# roller-shutter-rs485-double.net
KiCad netlist of a schematic drawn in EAGLE
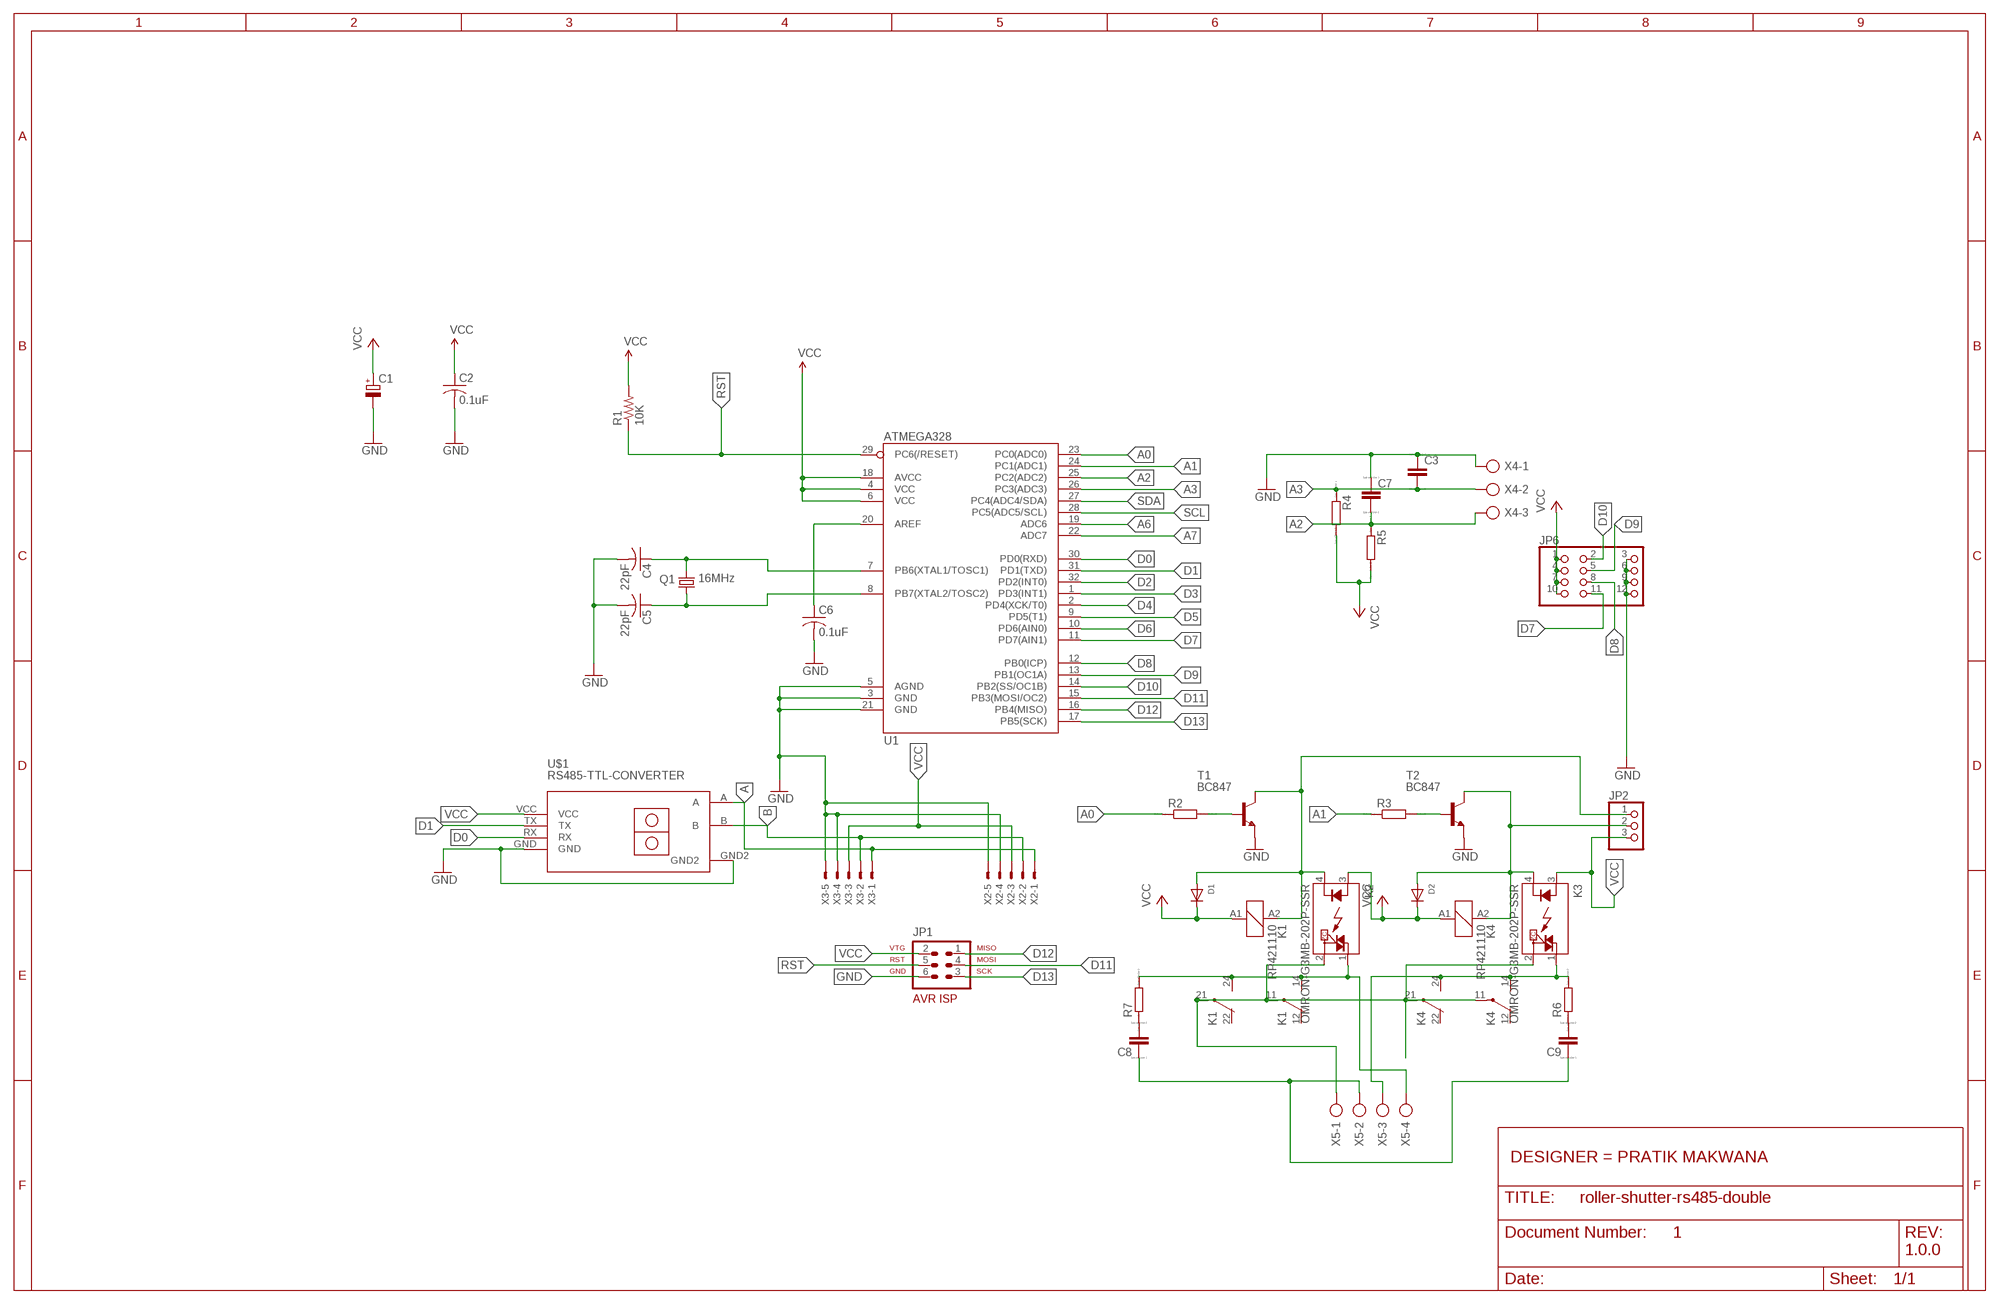
[diagram p0: schematic, sheet 1]

(export (version "E")
  (design (tool "Eeschema 10.0.6"))
  (components
    (comp (ref "C1")
      (value "CPOL-EUSANYO_SMD_C6")
      (footprint "eagle-import:SANYO-OSCON_SMD_C6")
      (libsource (lib "eagle-import") (part "CPOL-EUSANYO_SMD_C6"))
    )
    (comp (ref "C2")
      (value "0.1uF")
      (footprint "eagle-import:C0805")
      (libsource (lib "eagle-import") (part "C-USC0805"))
    )
    (comp (ref "C3") (value "C") (footprint "eagle-import:C0805") (libsource (lib "eagle-import") (part "C")))
    (comp (ref "C4")
      (value "22pF")
      (footprint "eagle-import:C1206")
      (libsource (lib "eagle-import") (part "C-USC1206"))
    )
    (comp (ref "C5")
      (value "22pF")
      (footprint "eagle-import:C1206")
      (libsource (lib "eagle-import") (part "C-USC1206"))
    )
    (comp (ref "C6")
      (value "0.1uF")
      (footprint "eagle-import:C0805")
      (libsource (lib "eagle-import") (part "C-USC0805"))
    )
    (comp (ref "C7") (value "C") (footprint "eagle-import:C0805") (libsource (lib "eagle-import") (part "C")))
    (comp (ref "C8")
      (value "CC1812")
      (footprint "eagle-import:C1812")
      (libsource (lib "eagle-import") (part "CC1812"))
    )
    (comp (ref "C9")
      (value "CC1812")
      (footprint "eagle-import:C1812")
      (libsource (lib "eagle-import") (part "CC1812"))
    )
    (comp (ref "D1")
      (value "DIODE_SOD-123FL")
      (footprint "eagle-import:SOD-123FL")
      (libsource (lib "eagle-import") (part "DIODE_SOD-123FL"))
    )
    (comp (ref "D2")
      (value "DIODE_SOD-123FL")
      (footprint "eagle-import:SOD-123FL")
      (libsource (lib "eagle-import") (part "DIODE_SOD-123FL"))
    )
    (comp (ref "JP1")
      (value "AVR-ISP-6")
      (footprint "eagle-import:AVR-ISP-6")
      (libsource (lib "eagle-import") (part "AVR-ISP-6"))
    )
    (comp (ref "JP2")
      (value "PINHD-1X3")
      (footprint "eagle-import:1X03")
      (libsource (lib "eagle-import") (part "PINHD-1X3"))
    )
    (comp (ref "JP6")
      (value "PINHD-3X4")
      (footprint "eagle-import:3X04")
      (libsource (lib "eagle-import") (part "PINHD-3X4"))
    )
    (comp (ref "K1")
      (value "RP421110")
      (footprint "eagle-import:RP420")
      (fields (field (name "MF") "TYCO ELECTRONICS"))
      (libsource (lib "eagle-import") (part "RP42?1110"))
    )
    (comp (ref "K2")
      (value "OMRON-G3MB-202P-SSR")
      (footprint "eagle-import:OMRON-G3MB-202P-SSR")
      (libsource (lib "eagle-import") (part "OMRON-G3MB-202P-SSR"))
    )
    (comp (ref "K3")
      (value "OMRON-G3MB-202P-SSR")
      (footprint "eagle-import:OMRON-G3MB-202P-SSR")
      (libsource (lib "eagle-import") (part "OMRON-G3MB-202P-SSR"))
    )
    (comp (ref "K4")
      (value "RP421110")
      (footprint "eagle-import:RP420")
      (fields (field (name "MF") "TYCO ELECTRONICS"))
      (libsource (lib "eagle-import") (part "RP42?1110"))
    )
    (comp (ref "Q1")
      (value "16MHz")
      (footprint "eagle-import:HC49_S")
      (libsource (lib "eagle-import") (part "CRYTALHC49S"))
    )
    (comp (ref "R1")
      (value "10K")
      (footprint "eagle-import:R1206")
      (libsource (lib "eagle-import") (part "R-US_R1206"))
    )
    (comp (ref "R2")
      (value "RR1206")
      (footprint "eagle-import:R1206")
      (libsource (lib "eagle-import") (part "RR1206"))
    )
    (comp (ref "R3")
      (value "RR1206")
      (footprint "eagle-import:R1206")
      (libsource (lib "eagle-import") (part "RR1206"))
    )
    (comp (ref "R4")
      (value "RR1206")
      (footprint "eagle-import:R1206")
      (libsource (lib "eagle-import") (part "RR1206"))
    )
    (comp (ref "R5")
      (value "RR1206")
      (footprint "eagle-import:R1206")
      (libsource (lib "eagle-import") (part "RR1206"))
    )
    (comp (ref "R6")
      (value "RR2512")
      (footprint "eagle-import:R2512")
      (libsource (lib "eagle-import") (part "RR2512"))
    )
    (comp (ref "R7")
      (value "RR2512")
      (footprint "eagle-import:R2512")
      (libsource (lib "eagle-import") (part "RR2512"))
    )
    (comp (ref "T1")
      (value "BC847")
      (footprint "eagle-import:SOT23")
      (libsource (lib "eagle-import") (part "BC847"))
    )
    (comp (ref "T2")
      (value "BC847")
      (footprint "eagle-import:SOT23")
      (libsource (lib "eagle-import") (part "BC847"))
    )
    (comp (ref "U$1")
      (value "RS485-TTL-CONVERTER")
      (footprint "eagle-import:RS485-TTL-CONVERTER")
      (libsource (lib "eagle-import") (part "RS485-TTL-CONVERTER"))
    )
    (comp (ref "U1")
      (value "ATMEGA328")
      (footprint "eagle-import:TQFP32-08")
      (libsource (lib "eagle-import") (part "ATMEGA328"))
    )
    (comp (ref "X2")
      (value "JST-XH-05-PIN-LONG-PAD")
      (footprint "eagle-import:JST-XH-05-PACKAGE-LONG-PAD")
      (libsource (lib "eagle-import") (part "JST-XH-05-PIN-LONG-PAD"))
    )
    (comp (ref "X3")
      (value "JST-XH-05-PIN-LONG-PAD")
      (footprint "eagle-import:JST-XH-05-PACKAGE-LONG-PAD")
      (libsource (lib "eagle-import") (part "JST-XH-05-PIN-LONG-PAD"))
    )
    (comp (ref "X4")
      (value "AK500/3")
      (footprint "eagle-import:AK500_3")
      (libsource (lib "eagle-import") (part "AK500/3"))
    )
    (comp (ref "X5")
      (value "AK500/4")
      (footprint "eagle-import:AK500_4")
      (libsource (lib "eagle-import") (part "AK500/4"))
    )
  )
  (nets
    (net (code "1") (name "A") (class "Default")
      (node (ref "U$1") (pin "A") (pinfunction "A_A") (pintype "passive"))
      (node (ref "X2") (pin "1") (pinfunction "S_1") (pintype "passive"))
      (node (ref "X3") (pin "1") (pinfunction "S_1") (pintype "passive"))
    )
    (net (code "2") (name "A0") (class "Default")
      (node (ref "R2") (pin "1") (pinfunction "1_1") (pintype "passive"))
      (node (ref "U1") (pin "23") (pinfunction "PC0(ADC0)_23") (pintype "bidirectional"))
    )
    (net (code "3") (name "A1") (class "Default")
      (node (ref "R3") (pin "1") (pinfunction "1_1") (pintype "passive"))
      (node (ref "U1") (pin "24") (pinfunction "PC1(ADC1)_24") (pintype "bidirectional"))
    )
    (net (code "4") (name "A2") (class "Default")
      (node (ref "C7") (pin "2") (pinfunction "2_2") (pintype "passive"))
      (node (ref "R5") (pin "1") (pinfunction "1_1") (pintype "passive"))
      (node (ref "U1") (pin "25") (pinfunction "PC2(ADC2)_25") (pintype "bidirectional"))
      (node (ref "X4") (pin "3") (pinfunction "KL_3") (pintype "passive"))
    )
    (net (code "5") (name "A3") (class "Default")
      (node (ref "C3") (pin "2") (pinfunction "2_2") (pintype "passive"))
      (node (ref "R4") (pin "1") (pinfunction "1_1") (pintype "passive"))
      (node (ref "U1") (pin "26") (pinfunction "PC3(ADC3)_26") (pintype "bidirectional"))
      (node (ref "X4") (pin "2") (pinfunction "KL_2") (pintype "passive"))
    )
    (net (code "6") (name "A6") (class "Default")
      (node (ref "U1") (pin "19") (pinfunction "ADC6_19") (pintype "bidirectional"))
    )
    (net (code "7") (name "A7") (class "Default")
      (node (ref "U1") (pin "22") (pinfunction "ADC7_22") (pintype "bidirectional"))
    )
    (net (code "8") (name "B") (class "Default")
      (node (ref "U$1") (pin "B") (pinfunction "B_B") (pintype "passive"))
      (node (ref "X2") (pin "2") (pinfunction "S_2") (pintype "passive"))
      (node (ref "X3") (pin "2") (pinfunction "S_2") (pintype "passive"))
    )
    (net (code "9") (name "D0") (class "Default")
      (node (ref "U$1") (pin "RX") (pinfunction "RX_RX") (pintype "passive"))
      (node (ref "U1") (pin "30") (pinfunction "PD0(RXD)_30") (pintype "bidirectional"))
    )
    (net (code "10") (name "D1") (class "Default")
      (node (ref "U$1") (pin "TX") (pinfunction "TX_TX") (pintype "passive"))
      (node (ref "U1") (pin "31") (pinfunction "PD1(TXD)_31") (pintype "bidirectional"))
    )
    (net (code "11") (name "D2") (class "Default")
      (node (ref "U1") (pin "32") (pinfunction "PD2(INT0)_32") (pintype "bidirectional"))
    )
    (net (code "12") (name "D3") (class "Default")
      (node (ref "U1") (pin "1") (pinfunction "PD3(INT1)_1") (pintype "bidirectional"))
    )
    (net (code "13") (name "D4") (class "Default")
      (node (ref "U1") (pin "2") (pinfunction "PD4(XCK/T0)_2") (pintype "bidirectional"))
    )
    (net (code "14") (name "D5") (class "Default")
      (node (ref "U1") (pin "9") (pinfunction "PD5(T1)_9") (pintype "bidirectional"))
    )
    (net (code "15") (name "D6") (class "Default")
      (node (ref "U1") (pin "10") (pinfunction "PD6(AIN0)_10") (pintype "bidirectional"))
    )
    (net (code "16") (name "D7") (class "Default")
      (node (ref "JP6") (pin "11") (pinfunction "11_11") (pintype "passive"))
      (node (ref "U1") (pin "11") (pinfunction "PD7(AIN1)_11") (pintype "bidirectional"))
    )
    (net (code "17") (name "D8") (class "Default")
      (node (ref "JP6") (pin "8") (pinfunction "8_8") (pintype "passive"))
      (node (ref "U1") (pin "12") (pinfunction "PB0(ICP)_12") (pintype "bidirectional"))
    )
    (net (code "18") (name "D9") (class "Default")
      (node (ref "JP6") (pin "5") (pinfunction "5_5") (pintype "passive"))
      (node (ref "U1") (pin "13") (pinfunction "PB1(OC1A)_13") (pintype "bidirectional"))
    )
    (net (code "19") (name "D10") (class "Default")
      (node (ref "JP6") (pin "2") (pinfunction "2_2") (pintype "passive"))
      (node (ref "U1") (pin "14") (pinfunction "PB2(SS/OC1B)_14") (pintype "bidirectional"))
    )
    (net (code "20") (name "D11") (class "Default")
      (node (ref "JP1") (pin "4") (pinfunction "4_4") (pintype "passive"))
      (node (ref "U1") (pin "15") (pinfunction "PB3(MOSI/OC2)_15") (pintype "bidirectional"))
    )
    (net (code "21") (name "D12") (class "Default")
      (node (ref "JP1") (pin "1") (pinfunction "1_1") (pintype "passive"))
      (node (ref "U1") (pin "16") (pinfunction "PB4(MISO)_16") (pintype "bidirectional"))
    )
    (net (code "22") (name "D13") (class "Default")
      (node (ref "JP1") (pin "3") (pinfunction "3_3") (pintype "passive"))
      (node (ref "U1") (pin "17") (pinfunction "PB5(SCK)_17") (pintype "bidirectional"))
    )
    (net (code "23") (name "GND") (class "Default")
      (node (ref "C1") (pin "-") (pinfunction "-_-") (pintype "passive"))
      (node (ref "C2") (pin "2") (pinfunction "2_2") (pintype "passive"))
      (node (ref "C3") (pin "1") (pinfunction "1_1") (pintype "passive"))
      (node (ref "C4") (pin "2") (pinfunction "2_2") (pintype "passive"))
      (node (ref "C5") (pin "2") (pinfunction "2_2") (pintype "passive"))
      (node (ref "C6") (pin "2") (pinfunction "2_2") (pintype "passive"))
      (node (ref "C7") (pin "1") (pinfunction "1_1") (pintype "passive"))
      (node (ref "JP1") (pin "6") (pinfunction "6_6") (pintype "passive"))
      (node (ref "JP6") (pin "12") (pinfunction "12_12") (pintype "passive"))
      (node (ref "JP6") (pin "3") (pinfunction "3_3") (pintype "passive"))
      (node (ref "JP6") (pin "6") (pinfunction "6_6") (pintype "passive"))
      (node (ref "JP6") (pin "9") (pinfunction "9_9") (pintype "passive"))
      (node (ref "T1") (pin "2") (pinfunction "E_2") (pintype "passive"))
      (node (ref "T2") (pin "2") (pinfunction "E_2") (pintype "passive"))
      (node (ref "U$1") (pin "GND") (pinfunction "GND_GND") (pintype "passive"))
      (node (ref "U$1") (pin "GND2") (pinfunction "GND2_GND2") (pintype "power_in"))
      (node (ref "U1") (pin "21") (pinfunction "GND_21") (pintype "bidirectional"))
      (node (ref "U1") (pin "3") (pinfunction "GND_3") (pintype "bidirectional"))
      (node (ref "U1") (pin "5") (pinfunction "AGND_5") (pintype "bidirectional"))
      (node (ref "X2") (pin "4") (pinfunction "S_4") (pintype "passive"))
      (node (ref "X2") (pin "5") (pinfunction "S_5") (pintype "passive"))
      (node (ref "X3") (pin "4") (pinfunction "S_4") (pintype "passive"))
      (node (ref "X3") (pin "5") (pinfunction "S_5") (pintype "passive"))
      (node (ref "X4") (pin "1") (pinfunction "KL_1") (pintype "passive"))
    )
    (net (code "24") (name "Net-(C8-Pad2)") (class "Default")
      (node (ref "C8") (pin "2") (pinfunction "2_2") (pintype "passive"))
      (node (ref "R7") (pin "1") (pinfunction "1_1") (pintype "passive"))
    )
    (net (code "25") (name "Net-(C9-Pad2)") (class "Default")
      (node (ref "C9") (pin "2") (pinfunction "2_2") (pintype "passive"))
      (node (ref "R6") (pin "1") (pinfunction "1_1") (pintype "passive"))
    )
    (net (code "26") (name "Net-(K1A-1)") (class "Default")
      (node (ref "D1") (pin "A") (pinfunction "A_A") (pintype "passive"))
      (node (ref "JP2") (pin "1") (pinfunction "1_1") (pintype "passive"))
      (node (ref "K1") (pin "A2") (pinfunction "1_A2") (pintype "passive"))
      (node (ref "K2") (pin "4") (pinfunction "K_4") (pintype "passive"))
      (node (ref "T1") (pin "3") (pinfunction "C_3") (pintype "passive"))
    )
    (net (code "27") (name "Net-(K1B-P)") (class "Default")
      (node (ref "K1") (pin "11") (pinfunction "P_11") (pintype "passive"))
      (node (ref "K1") (pin "21") (pinfunction "P_21") (pintype "passive"))
      (node (ref "K2") (pin "2") (pinfunction "DS2_2") (pintype "passive"))
      (node (ref "K3") (pin "2") (pinfunction "DS2_2") (pintype "passive"))
      (node (ref "K4") (pin "11") (pinfunction "P_11") (pintype "passive"))
      (node (ref "K4") (pin "21") (pinfunction "P_21") (pintype "passive"))
      (node (ref "X5") (pin "1") (pinfunction "KL_1") (pintype "passive"))
    )
    (net (code "28") (name "Net-(K1B-S)") (class "Default")
      (node (ref "K1") (pin "14") (pinfunction "S_14") (pintype "passive"))
      (node (ref "K1") (pin "24") (pinfunction "S_24") (pintype "passive"))
      (node (ref "K2") (pin "1") (pinfunction "DS1_1") (pintype "passive"))
      (node (ref "R7") (pin "2") (pinfunction "2_2") (pintype "passive"))
      (node (ref "X5") (pin "4") (pinfunction "KL_4") (pintype "passive"))
    )
    (net (code "29") (name "Net-(K3-DS1)") (class "Default")
      (node (ref "K3") (pin "1") (pinfunction "DS1_1") (pintype "passive"))
      (node (ref "K4") (pin "14") (pinfunction "S_14") (pintype "passive"))
      (node (ref "K4") (pin "24") (pinfunction "S_24") (pintype "passive"))
      (node (ref "R6") (pin "2") (pinfunction "2_2") (pintype "passive"))
      (node (ref "X5") (pin "3") (pinfunction "KL_3") (pintype "passive"))
    )
    (net (code "30") (name "Net-(K3-K)") (class "Default")
      (node (ref "D2") (pin "A") (pinfunction "A_A") (pintype "passive"))
      (node (ref "JP2") (pin "2") (pinfunction "2_2") (pintype "passive"))
      (node (ref "K3") (pin "4") (pinfunction "K_4") (pintype "passive"))
      (node (ref "K4") (pin "A2") (pinfunction "1_A2") (pintype "passive"))
      (node (ref "T2") (pin "3") (pinfunction "C_3") (pintype "passive"))
    )
    (net (code "31") (name "Net-(T1-B)") (class "Default")
      (node (ref "R2") (pin "2") (pinfunction "2_2") (pintype "passive"))
      (node (ref "T1") (pin "1") (pinfunction "B_1") (pintype "passive"))
    )
    (net (code "32") (name "Net-(T2-B)") (class "Default")
      (node (ref "R3") (pin "2") (pinfunction "2_2") (pintype "passive"))
      (node (ref "T2") (pin "1") (pinfunction "B_1") (pintype "passive"))
    )
    (net (code "33") (name "Net-(U1-AREF)") (class "Default")
      (node (ref "C6") (pin "1") (pinfunction "1_1") (pintype "passive"))
      (node (ref "U1") (pin "20") (pinfunction "AREF_20") (pintype "bidirectional"))
    )
    (net (code "34") (name "Net-(U1-PB6(XTAL1{slash}TOSC1))") (class "Default")
      (node (ref "C4") (pin "1") (pinfunction "1_1") (pintype "passive"))
      (node (ref "Q1") (pin "2") (pinfunction "2_2") (pintype "passive"))
      (node (ref "U1") (pin "7") (pinfunction "PB6(XTAL1/TOSC1)_7") (pintype "bidirectional"))
    )
    (net (code "35") (name "Net-(U1-PB7(XTAL2{slash}TOSC2))") (class "Default")
      (node (ref "C5") (pin "1") (pinfunction "1_1") (pintype "passive"))
      (node (ref "Q1") (pin "1") (pinfunction "1_1") (pintype "passive"))
      (node (ref "U1") (pin "8") (pinfunction "PB7(XTAL2/TOSC2)_8") (pintype "bidirectional"))
    )
    (net (code "36") (name "Net-(X5B-KL)") (class "Default")
      (node (ref "C8") (pin "1") (pinfunction "1_1") (pintype "passive"))
      (node (ref "C9") (pin "1") (pinfunction "1_1") (pintype "passive"))
      (node (ref "X5") (pin "2") (pinfunction "KL_2") (pintype "passive"))
    )
    (net (code "37") (name "RST") (class "Default")
      (node (ref "JP1") (pin "5") (pinfunction "5_5") (pintype "passive"))
      (node (ref "R1") (pin "1") (pinfunction "1_1") (pintype "passive"))
      (node (ref "U1") (pin "29") (pinfunction "PC6(/RESET)_29") (pintype "bidirectional"))
    )
    (net (code "38") (name "SCL") (class "Default")
      (node (ref "U1") (pin "28") (pinfunction "PC5(ADC5/SCL)_28") (pintype "bidirectional"))
    )
    (net (code "39") (name "SDA") (class "Default")
      (node (ref "U1") (pin "27") (pinfunction "PC4(ADC4/SDA)_27") (pintype "bidirectional"))
    )
    (net (code "40") (name "VCC") (class "Default")
      (node (ref "C1") (pin "+") (pinfunction "+_+") (pintype "passive"))
      (node (ref "C2") (pin "1") (pinfunction "1_1") (pintype "passive"))
      (node (ref "D1") (pin "C") (pinfunction "C_C") (pintype "passive"))
      (node (ref "D2") (pin "C") (pinfunction "C_C") (pintype "passive"))
      (node (ref "JP1") (pin "2") (pinfunction "2_2") (pintype "passive"))
      (node (ref "JP2") (pin "3") (pinfunction "3_3") (pintype "passive"))
      (node (ref "JP6") (pin "1") (pinfunction "1_1") (pintype "passive"))
      (node (ref "JP6") (pin "10") (pinfunction "10_10") (pintype "passive"))
      (node (ref "JP6") (pin "4") (pinfunction "4_4") (pintype "passive"))
      (node (ref "JP6") (pin "7") (pinfunction "7_7") (pintype "passive"))
      (node (ref "K1") (pin "A1") (pinfunction "2_A1") (pintype "passive"))
      (node (ref "K2") (pin "3") (pinfunction "A_3") (pintype "passive"))
      (node (ref "K3") (pin "3") (pinfunction "A_3") (pintype "passive"))
      (node (ref "K4") (pin "A1") (pinfunction "2_A1") (pintype "passive"))
      (node (ref "R1") (pin "2") (pinfunction "2_2") (pintype "passive"))
      (node (ref "R4") (pin "2") (pinfunction "2_2") (pintype "passive"))
      (node (ref "R5") (pin "2") (pinfunction "2_2") (pintype "passive"))
      (node (ref "U$1") (pin "VCC") (pinfunction "VCC_VCC") (pintype "passive"))
      (node (ref "U1") (pin "18") (pinfunction "AVCC_18") (pintype "bidirectional"))
      (node (ref "U1") (pin "4") (pinfunction "VCC_4") (pintype "bidirectional"))
      (node (ref "U1") (pin "6") (pinfunction "VCC_6") (pintype "bidirectional"))
      (node (ref "X2") (pin "3") (pinfunction "S_3") (pintype "passive"))
      (node (ref "X3") (pin "3") (pinfunction "S_3") (pintype "passive"))
    )
    (net (code "41") (name "unconnected-(K1B-O-Pad12)") (class "Default")
      (node (ref "K1") (pin "12") (pinfunction "O_12") (pintype "passive"))
    )
    (net (code "42") (name "unconnected-(K1C-O-Pad22)") (class "Default")
      (node (ref "K1") (pin "22") (pinfunction "O_22") (pintype "passive"))
    )
    (net (code "43") (name "unconnected-(K4B-O-Pad12)") (class "Default")
      (node (ref "K4") (pin "12") (pinfunction "O_12") (pintype "passive"))
    )
    (net (code "44") (name "unconnected-(K4C-O-Pad22)") (class "Default")
      (node (ref "K4") (pin "22") (pinfunction "O_22") (pintype "passive"))
    )
  )
)
